# Deck_SchV1.net
KiCad netlist of a schematic drawn in Altium Designer
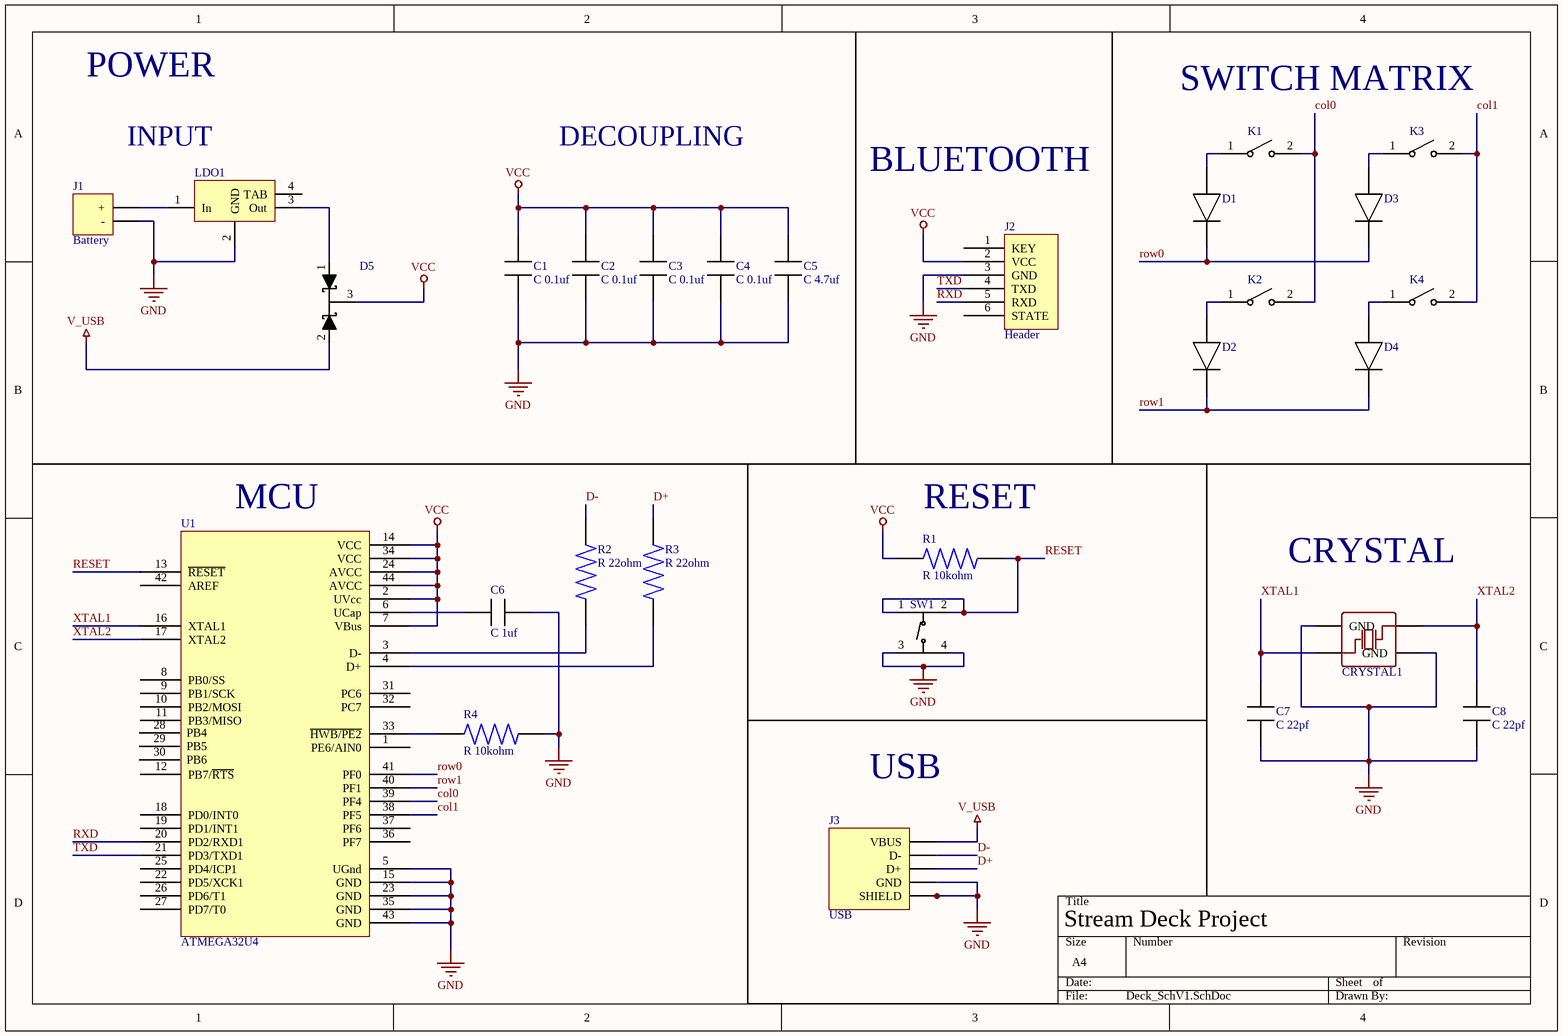
[diagram p0: Deck_SchV1.SchDoc]

(export (version "E")
  (design (tool "Eeschema 10.0.6"))
  (components
    (comp (ref "C1")
      (value "C 0.1uf")
      (footprint "C0805")
      (fields
        (field (name "MANUFACTURER") "Yageo")
        (field (name "MANUFACTURER PART NUMBER") "CC0805ZRY5V9BB104")
        (field (name "TOLERANCE") "80%")
      )
      (libsource (lib "Deck_SchlibV2") (part "CC0805ZRY5V9BB104"))
    )
    (comp (ref "C2")
      (value "C 0.1uf")
      (footprint "C0805")
      (fields
        (field (name "MANUFACTURER") "Yageo")
        (field (name "MANUFACTURER PART NUMBER") "CC0805ZRY5V9BB104")
        (field (name "TOLERANCE") "80%")
      )
      (libsource (lib "Deck_SchlibV2") (part "CC0805ZRY5V9BB104"))
    )
    (comp (ref "C3")
      (value "C 0.1uf")
      (footprint "C0805")
      (fields
        (field (name "MANUFACTURER") "Yageo")
        (field (name "MANUFACTURER PART NUMBER") "CC0805ZRY5V9BB104")
        (field (name "TOLERANCE") "80%")
      )
      (libsource (lib "Deck_SchlibV2") (part "CC0805ZRY5V9BB104"))
    )
    (comp (ref "C4")
      (value "C 0.1uf")
      (footprint "C0805")
      (fields
        (field (name "MANUFACTURER") "Yageo")
        (field (name "MANUFACTURER PART NUMBER") "CC0805ZRY5V9BB104")
        (field (name "TOLERANCE") "80%")
      )
      (libsource (lib "Deck_SchlibV2") (part "CC0805ZRY5V9BB104"))
    )
    (comp (ref "C5")
      (value "C 4.7uf")
      (footprint "C0805")
      (fields
        (field (name "MANUFACTURER") "Samsung")
        (field (name "MANUFACTURER PART NUMBER") "CL21A475KAQNNNE")
        (field (name "TOLERANCE") "10%")
      )
      (libsource (lib "Deck_SchlibV2") (part "CL21A475KAQNNNE"))
    )
    (comp (ref "C6")
      (value "C 1uf")
      (footprint "C0805")
      (fields
        (field (name "MANUFACTURER") "Samsung")
        (field (name "MANUFACTURER PART NUMBER") "CL21B105KBFNNNE")
        (field (name "TOLERANCE") "10%")
      )
      (libsource (lib "Deck_SchlibV2") (part "CL21B105KBFNNNE"))
    )
    (comp (ref "C7")
      (value "C 22pf")
      (footprint "C0805")
      (description "Cap Ceramic 22pF 50V C0G 5% SMD 0805 125C T/R")
      (fields
        (field (name "MANUFACTURER") "Samsung")
        (field (name "MANUFACTURER PART NUMBER") "CL21C220JBANNNC")
      )
      (libsource (lib "Deck_SchlibV2") (part "CL21C220JBANNNC"))
    )
    (comp (ref "C8")
      (value "C 22pf")
      (footprint "C0805")
      (description "Cap Ceramic 22pF 50V C0G 5% SMD 0805 125C T/R")
      (fields
        (field (name "MANUFACTURER") "Samsung")
        (field (name "MANUFACTURER PART NUMBER") "CL21C220JBANNNC")
      )
      (libsource (lib "Deck_SchlibV2") (part "CL21C220JBANNNC"))
    )
    (comp (ref "CRYSTAL1")
      (value "Crystal")
      (footprint "CRYSTAL-SMD_4P-L3.2-W2.5-BL")
      (fields (field (name "MANUFACTURER") "Seiko") (field (name "MANUFACTURER PART NUMBER") "X1E0000210264"))
      (libsource (lib "Deck_SchlibV2") (part "X1E0000210264"))
    )
    (comp (ref "D1")
      (value "Diode")
      (footprint "Diode")
      (description "MICRO COMMERCIAL COMPONENTS - 1N4148W-TP - SWITCHING DIODE, 150mA, 100V, SOD123, FU")
      (fields (field (name "MANUFACTURER") "MCC") (field (name "MANUFACTURER PART NUMBER") "1N4148W-TP"))
      (libsource (lib "Deck_SchlibV2") (part "1N4148W-TP"))
    )
    (comp (ref "D2")
      (value "Diode")
      (footprint "Diode")
      (description "MICRO COMMERCIAL COMPONENTS - 1N4148W-TP - SWITCHING DIODE, 150mA, 100V, SOD123, FU")
      (fields (field (name "MANUFACTURER") "MCC") (field (name "MANUFACTURER PART NUMBER") "1N4148W-TP"))
      (libsource (lib "Deck_SchlibV2") (part "1N4148W-TP"))
    )
    (comp (ref "D3")
      (value "Diode")
      (footprint "Diode")
      (description "MICRO COMMERCIAL COMPONENTS - 1N4148W-TP - SWITCHING DIODE, 150mA, 100V, SOD123, FU")
      (fields (field (name "MANUFACTURER") "MCC") (field (name "MANUFACTURER PART NUMBER") "1N4148W-TP"))
      (libsource (lib "Deck_SchlibV2") (part "1N4148W-TP"))
    )
    (comp (ref "D4")
      (value "Diode")
      (footprint "Diode")
      (description "MICRO COMMERCIAL COMPONENTS - 1N4148W-TP - SWITCHING DIODE, 150mA, 100V, SOD123, FU")
      (fields (field (name "MANUFACTURER") "MCC") (field (name "MANUFACTURER PART NUMBER") "1N4148W-TP"))
      (libsource (lib "Deck_SchlibV2") (part "1N4148W-TP"))
    )
    (comp (ref "D5")
      (value "Schottky diode")
      (footprint "SOT95P237X111-3N")
      (description "Diode Schottky 30V 0.2A 3-Pin SOT-23 T/R")
      (fields
        (field (name "MANUFACTURER") "ON Semiconductor")
        (field (name "MANUFACTURER PART NUMBER") "BAT54CLT1G")
      )
      (libsource (lib "Deck_SchlibV2") (part "BAT54CLT1G"))
    )
    (comp (ref "J1")
      (value "Battery")
      (footprint "HDR-TH_2P-P2.54-V-M-1")
      (description "CONN HEADER VERT 2POS 2.54MM")
      (fields (field (name "MANUFACTURER") "Molex") (field (name "MANUFACTURER PART NUMBER") "22-28-4020"))
      (libsource (lib "Deck_SchlibV2") (part "22-28-4020"))
    )
    (comp (ref "J2")
      (value "Header")
      (footprint "HDR-TH_6P-P2.54-H-W8.6_A2541HWR-6P")
      (fields
        (field (name "MANUFACTURER") "CJT Connectors")
        (field (name "MANUFACTURER PART NUMBER") "A2541HWR-6P")
      )
      (libsource (lib "Deck_SchlibV2") (part "A2541HWR-6P"))
    )
    (comp (ref "J3")
      (value "USB")
      (footprint "USB")
      (description "Conn Mini USB 2.0 Type B RCP 5 POS 0.8mm Solder RA SMD 5 Terminal 1 Port Embossed T/R")
      (fields
        (field (name "MANUFACTURER") "Hirose")
        (field (name "MANUFACTURER PART NUMBER") "UX60SC-MB-5S8")
      )
      (libsource (lib "Deck_SchlibV2") (part "UX60SC-MB-5S8"))
    )
    (comp (ref "K1")
      (value "Switch")
      (footprint "Mx_Alps_100")
      (libsource (lib "Deck_SchlibV2") (part "Keyboard Switch"))
    )
    (comp (ref "K2")
      (value "Switch")
      (footprint "Mx_Alps_100")
      (libsource (lib "Deck_SchlibV2") (part "Keyboard Switch"))
    )
    (comp (ref "K3")
      (value "Switch")
      (footprint "Mx_Alps_100")
      (libsource (lib "Deck_SchlibV2") (part "Keyboard Switch"))
    )
    (comp (ref "K4")
      (value "Switch")
      (footprint "Mx_Alps_100")
      (libsource (lib "Deck_SchlibV2") (part "Keyboard Switch"))
    )
    (comp (ref "LDO1")
      (value "5V regulator")
      (footprint "SOT-223_L6.5-W3.5-P2.30-LS7.0-BR")
      (fields
        (field (name "MANUFACTURER") "Advanced Monolithic Systems")
        (field (name "MANUFACTURER PART NUMBER") "AMS1117-5.0")
      )
      (libsource (lib "Deck_SchlibV2") (part "AMS1117-5.0"))
    )
    (comp (ref "R1")
      (value "R 10kohm")
      (footprint "R0805")
      (fields
        (field (name "MANUFACTURER") "Uniroyal")
        (field (name "MANUFACTURER PART NUMBER") "0805W8F1002T5E")
      )
      (libsource (lib "Deck_SchlibV2") (part "0805W8F1002T5E"))
    )
    (comp (ref "R2")
      (value "R 22ohm")
      (footprint "R0805")
      (fields
        (field (name "MANUFACTURER") "Uniroyal")
        (field (name "MANUFACTURER PART NUMBER") "0805W8F220JT5E")
      )
      (libsource (lib "Deck_SchlibV2") (part "0805W8F220JT5E"))
    )
    (comp (ref "R3")
      (value "R 22ohm")
      (footprint "R0805")
      (fields
        (field (name "MANUFACTURER") "Uniroyal")
        (field (name "MANUFACTURER PART NUMBER") "0805W8F220JT5E")
      )
      (libsource (lib "Deck_SchlibV2") (part "0805W8F220JT5E"))
    )
    (comp (ref "R4")
      (value "R 10kohm")
      (footprint "R0805")
      (fields
        (field (name "MANUFACTURER") "Uniroyal")
        (field (name "MANUFACTURER PART NUMBER") "0805W8F1002T5E")
      )
      (libsource (lib "Deck_SchlibV2") (part "0805W8F1002T5E"))
    )
    (comp (ref "SW1")
      (value "Button")
      (footprint "SW-SMD_4P-L5.1-W5.1-P3.70-LS6.5-TL-2")
      (fields
        (field (name "MANUFACTURER") "XKB Connectivity")
        (field (name "MANUFACTURER PART NUMBER") "TS-1187A-B-A-B")
      )
      (libsource (lib "Deck_SchlibV2") (part "TS-1187A-B-A-B"))
    )
    (comp (ref "U1")
      (value "ATMEGA32U4")
      (footprint "ATMEGA32U2-AUR")
      (description "IC MCU 8BIT 32KB FLASH 32TQFP")
      (fields
        (field (name "MANUFACTURER") "Microchip / Atmel")
        (field (name "MANUFACTURER PART NUMBER") "ATMEGA32U2-AUR")
      )
      (libsource (lib "Deck_SchlibV2") (part "ATMEGA32U2-AUR"))
    )
  )
  (nets
    (net (code "1") (name "/D+") (class "Default")
      (node (ref "J3") (pin "3") (pinfunction "D+_3") (pintype "passive"))
      (node (ref "R3") (pin "2") (pinfunction "57_2") (pintype "passive"))
    )
    (net (code "2") (name "/D-") (class "Default")
      (node (ref "J3") (pin "2") (pinfunction "D-_2") (pintype "passive"))
      (node (ref "R2") (pin "2") (pinfunction "57_2") (pintype "passive"))
    )
    (net (code "3") (name "/RESET") (class "Default")
      (node (ref "R1") (pin "2") (pinfunction "57_2") (pintype "passive"))
      (node (ref "SW1") (pin "1") (pinfunction "A_1") (pintype "passive"))
      (node (ref "SW1") (pin "2") (pinfunction "B_2") (pintype "passive"))
      (node (ref "U1") (pin "13") (pinfunction "~{RESET}_13") (pintype "passive"))
    )
    (net (code "4") (name "/RXD") (class "Default")
      (node (ref "J2") (pin "5") (pinfunction "RXD_5") (pintype "passive"))
      (node (ref "U1") (pin "20") (pinfunction "PD2/RXD1_20") (pintype "passive"))
    )
    (net (code "5") (name "/TXD") (class "Default")
      (node (ref "J2") (pin "4") (pinfunction "TXD_4") (pintype "passive"))
      (node (ref "U1") (pin "21") (pinfunction "PD3/TXD1_21") (pintype "passive"))
    )
    (net (code "6") (name "/XTAL1") (class "Default")
      (node (ref "C7") (pin "2") (pinfunction "54_2") (pintype "passive"))
      (node (ref "CRYSTAL1") (pin "1") (pinfunction "OSC1_1") (pintype "passive"))
      (node (ref "U1") (pin "16") (pinfunction "XTAL1_16") (pintype "passive"))
    )
    (net (code "7") (name "/XTAL2") (class "Default")
      (node (ref "C8") (pin "2") (pinfunction "54_2") (pintype "passive"))
      (node (ref "CRYSTAL1") (pin "3") (pinfunction "OSC2_3") (pintype "passive"))
      (node (ref "U1") (pin "17") (pinfunction "XTAL2_17") (pintype "passive"))
    )
    (net (code "8") (name "/col0") (class "Default")
      (node (ref "K1") (pin "2") (pinfunction "2_2") (pintype "passive"))
      (node (ref "K2") (pin "2") (pinfunction "2_2") (pintype "passive"))
      (node (ref "U1") (pin "39") (pinfunction "PF4_39") (pintype "passive"))
    )
    (net (code "9") (name "/col1") (class "Default")
      (node (ref "K3") (pin "2") (pinfunction "2_2") (pintype "passive"))
      (node (ref "K4") (pin "2") (pinfunction "2_2") (pintype "passive"))
      (node (ref "U1") (pin "38") (pinfunction "PF5_38") (pintype "passive"))
    )
    (net (code "10") (name "/row0") (class "Default")
      (node (ref "D1") (pin "2") (pinfunction "-_2") (pintype "passive"))
      (node (ref "D3") (pin "2") (pinfunction "-_2") (pintype "passive"))
      (node (ref "U1") (pin "41") (pinfunction "PF0_41") (pintype "passive"))
    )
    (net (code "11") (name "/row1") (class "Default")
      (node (ref "D2") (pin "2") (pinfunction "-_2") (pintype "passive"))
      (node (ref "D4") (pin "2") (pinfunction "-_2") (pintype "passive"))
      (node (ref "U1") (pin "40") (pinfunction "PF1_40") (pintype "passive"))
    )
    (net (code "12") (name "GND") (class "Default")
      (node (ref "C1") (pin "1") (pinfunction "55_1") (pintype "passive"))
      (node (ref "C2") (pin "1") (pinfunction "55_1") (pintype "passive"))
      (node (ref "C3") (pin "1") (pinfunction "55_1") (pintype "passive"))
      (node (ref "C4") (pin "1") (pinfunction "55_1") (pintype "passive"))
      (node (ref "C5") (pin "1") (pinfunction "55_1") (pintype "passive"))
      (node (ref "C6") (pin "1") (pinfunction "55_1") (pintype "passive"))
      (node (ref "C7") (pin "1") (pinfunction "55_1") (pintype "passive"))
      (node (ref "C8") (pin "1") (pinfunction "55_1") (pintype "passive"))
      (node (ref "CRYSTAL1") (pin "2") (pinfunction "GND_2") (pintype "passive"))
      (node (ref "CRYSTAL1") (pin "4") (pinfunction "GND_4") (pintype "passive"))
      (node (ref "J1") (pin "2") (pinfunction "-_2") (pintype "passive"))
      (node (ref "J2") (pin "3") (pinfunction "GND_3") (pintype "passive"))
      (node (ref "J3") (pin "4") (pinfunction "GND_4") (pintype "passive"))
      (node (ref "J3") (pin "5") (pinfunction "SHIELD_5") (pintype "passive"))
      (node (ref "J3") (pin "S1") (pinfunction "6_S1") (pintype "passive"))
      (node (ref "J3") (pin "S2") (pinfunction "6_S2") (pintype "passive"))
      (node (ref "J3") (pin "S3") (pinfunction "6_S3") (pintype "passive"))
      (node (ref "J3") (pin "S4") (pinfunction "6_S4") (pintype "passive"))
      (node (ref "LDO1") (pin "2") (pinfunction "GND_2") (pintype "passive"))
      (node (ref "R4") (pin "2") (pinfunction "57_2") (pintype "passive"))
      (node (ref "SW1") (pin "3") (pinfunction "C_3") (pintype "passive"))
      (node (ref "SW1") (pin "4") (pinfunction "D_4") (pintype "passive"))
      (node (ref "U1") (pin "15") (pinfunction "GND_15") (pintype "passive"))
      (node (ref "U1") (pin "23") (pinfunction "GND_23") (pintype "passive"))
      (node (ref "U1") (pin "35") (pinfunction "GND_35") (pintype "passive"))
      (node (ref "U1") (pin "43") (pinfunction "GND_43") (pintype "passive"))
      (node (ref "U1") (pin "5") (pinfunction "UGnd_5") (pintype "passive"))
    )
    (net (code "13") (name "Net-(C6-54)") (class "Default")
      (node (ref "C6") (pin "2") (pinfunction "54_2") (pintype "passive"))
      (node (ref "U1") (pin "6") (pinfunction "UCap_6") (pintype "passive"))
    )
    (net (code "14") (name "Net-(D1-+)") (class "Default")
      (node (ref "D1") (pin "1") (pinfunction "+_1") (pintype "passive"))
      (node (ref "K1") (pin "1") (pinfunction "1_1") (pintype "passive"))
    )
    (net (code "15") (name "Net-(D2-+)") (class "Default")
      (node (ref "D2") (pin "1") (pinfunction "+_1") (pintype "passive"))
      (node (ref "K2") (pin "1") (pinfunction "1_1") (pintype "passive"))
    )
    (net (code "16") (name "Net-(D3-+)") (class "Default")
      (node (ref "D3") (pin "1") (pinfunction "+_1") (pintype "passive"))
      (node (ref "K3") (pin "1") (pinfunction "1_1") (pintype "passive"))
    )
    (net (code "17") (name "Net-(D4-+)") (class "Default")
      (node (ref "D4") (pin "1") (pinfunction "+_1") (pintype "passive"))
      (node (ref "K4") (pin "1") (pinfunction "1_1") (pintype "passive"))
    )
    (net (code "18") (name "Net-(D5-64)") (class "Default")
      (node (ref "D5") (pin "1") (pinfunction "64_1") (pintype "passive"))
      (node (ref "LDO1") (pin "3") (pinfunction "Out_3") (pintype "passive"))
    )
    (net (code "19") (name "Net-(J1-+)") (class "Default")
      (node (ref "J1") (pin "1") (pinfunction "+_1") (pintype "passive"))
      (node (ref "LDO1") (pin "1") (pinfunction "In_1") (pintype "passive"))
    )
    (net (code "20") (name "Net-(R2-56)") (class "Default")
      (node (ref "R2") (pin "1") (pinfunction "56_1") (pintype "passive"))
      (node (ref "U1") (pin "3") (pinfunction "D-_3") (pintype "passive"))
    )
    (net (code "21") (name "Net-(R3-56)") (class "Default")
      (node (ref "R3") (pin "1") (pinfunction "56_1") (pintype "passive"))
      (node (ref "U1") (pin "4") (pinfunction "D+_4") (pintype "passive"))
    )
    (net (code "22") (name "Net-(R4-56)") (class "Default")
      (node (ref "R4") (pin "1") (pinfunction "56_1") (pintype "passive"))
      (node (ref "U1") (pin "33") (pinfunction "~{HWB/PE2}_33") (pintype "passive"))
    )
    (net (code "23") (name "VCC") (class "Default")
      (node (ref "C1") (pin "2") (pinfunction "54_2") (pintype "passive"))
      (node (ref "C2") (pin "2") (pinfunction "54_2") (pintype "passive"))
      (node (ref "C3") (pin "2") (pinfunction "54_2") (pintype "passive"))
      (node (ref "C4") (pin "2") (pinfunction "54_2") (pintype "passive"))
      (node (ref "C5") (pin "2") (pinfunction "54_2") (pintype "passive"))
      (node (ref "D5") (pin "3") (pinfunction "66_3") (pintype "passive"))
      (node (ref "J2") (pin "2") (pinfunction "VCC_2") (pintype "passive"))
      (node (ref "R1") (pin "1") (pinfunction "56_1") (pintype "passive"))
      (node (ref "U1") (pin "14") (pinfunction "VCC_14") (pintype "passive"))
      (node (ref "U1") (pin "2") (pinfunction "UVcc_2") (pintype "passive"))
      (node (ref "U1") (pin "24") (pinfunction "AVCC_24") (pintype "passive"))
      (node (ref "U1") (pin "34") (pinfunction "VCC_34") (pintype "passive"))
      (node (ref "U1") (pin "44") (pinfunction "AVCC_44") (pintype "passive"))
      (node (ref "U1") (pin "7") (pinfunction "VBus_7") (pintype "passive"))
    )
    (net (code "24") (name "V_USB") (class "Default")
      (node (ref "D5") (pin "2") (pinfunction "65_2") (pintype "passive"))
      (node (ref "J3") (pin "1") (pinfunction "VBUS_1") (pintype "passive"))
    )
    (net (code "25") (name "unconnected-(J2-KEY-Pad1)") (class "Default")
      (node (ref "J2") (pin "1") (pinfunction "KEY_1") (pintype "passive"))
    )
    (net (code "26") (name "unconnected-(J2-STATE-Pad6)") (class "Default")
      (node (ref "J2") (pin "6") (pinfunction "STATE_6") (pintype "passive"))
    )
    (net (code "27") (name "unconnected-(LDO1-TAB-Pad4)") (class "Default")
      (node (ref "LDO1") (pin "4") (pinfunction "TAB_4") (pintype "passive"))
    )
    (net (code "28") (name "unconnected-(U1-AREF-Pad42)") (class "Default")
      (node (ref "U1") (pin "42") (pinfunction "AREF_42") (pintype "passive"))
    )
    (net (code "29") (name "unconnected-(U1-PB0{slash}SS-Pad8)") (class "Default")
      (node (ref "U1") (pin "8") (pinfunction "PB0/SS_8") (pintype "passive"))
    )
    (net (code "30") (name "unconnected-(U1-PB1{slash}SCK-Pad9)") (class "Default")
      (node (ref "U1") (pin "9") (pinfunction "PB1/SCK_9") (pintype "passive"))
    )
    (net (code "31") (name "unconnected-(U1-PB2{slash}MOSI-Pad10)") (class "Default")
      (node (ref "U1") (pin "10") (pinfunction "PB2/MOSI_10") (pintype "passive"))
    )
    (net (code "32") (name "unconnected-(U1-PB3{slash}MISO-Pad11)") (class "Default")
      (node (ref "U1") (pin "11") (pinfunction "PB3/MISO_11") (pintype "passive"))
    )
    (net (code "33") (name "unconnected-(U1-PB4-Pad28)") (class "Default")
      (node (ref "U1") (pin "28") (pinfunction "PB4_28") (pintype "passive"))
    )
    (net (code "34") (name "unconnected-(U1-PB5-Pad29)") (class "Default")
      (node (ref "U1") (pin "29") (pinfunction "PB5_29") (pintype "passive"))
    )
    (net (code "35") (name "unconnected-(U1-PB6-Pad30)") (class "Default")
      (node (ref "U1") (pin "30") (pinfunction "PB6_30") (pintype "passive"))
    )
    (net (code "36") (name "unconnected-(U1-PB7{slash}~{RTS}-Pad12)") (class "Default")
      (node (ref "U1") (pin "12") (pinfunction "PB7/~{RTS}_12") (pintype "passive"))
    )
    (net (code "37") (name "unconnected-(U1-PC6-Pad31)") (class "Default")
      (node (ref "U1") (pin "31") (pinfunction "PC6_31") (pintype "passive"))
    )
    (net (code "38") (name "unconnected-(U1-PC7-Pad32)") (class "Default")
      (node (ref "U1") (pin "32") (pinfunction "PC7_32") (pintype "passive"))
    )
    (net (code "39") (name "unconnected-(U1-PD0{slash}INT0-Pad18)") (class "Default")
      (node (ref "U1") (pin "18") (pinfunction "PD0/INT0_18") (pintype "passive"))
    )
    (net (code "40") (name "unconnected-(U1-PD1{slash}INT1-Pad19)") (class "Default")
      (node (ref "U1") (pin "19") (pinfunction "PD1/INT1_19") (pintype "passive"))
    )
    (net (code "41") (name "unconnected-(U1-PD4{slash}ICP1-Pad25)") (class "Default")
      (node (ref "U1") (pin "25") (pinfunction "PD4/ICP1_25") (pintype "passive"))
    )
    (net (code "42") (name "unconnected-(U1-PD5{slash}XCK1-Pad22)") (class "Default")
      (node (ref "U1") (pin "22") (pinfunction "PD5/XCK1_22") (pintype "passive"))
    )
    (net (code "43") (name "unconnected-(U1-PD6{slash}T1-Pad26)") (class "Default")
      (node (ref "U1") (pin "26") (pinfunction "PD6/T1_26") (pintype "passive"))
    )
    (net (code "44") (name "unconnected-(U1-PD7{slash}T0-Pad27)") (class "Default")
      (node (ref "U1") (pin "27") (pinfunction "PD7/T0_27") (pintype "passive"))
    )
    (net (code "45") (name "unconnected-(U1-PE6{slash}AIN0-Pad1)") (class "Default")
      (node (ref "U1") (pin "1") (pinfunction "PE6/AIN0_1") (pintype "passive"))
    )
    (net (code "46") (name "unconnected-(U1-PF6-Pad37)") (class "Default")
      (node (ref "U1") (pin "37") (pinfunction "PF6_37") (pintype "passive"))
    )
    (net (code "47") (name "unconnected-(U1-PF7-Pad36)") (class "Default")
      (node (ref "U1") (pin "36") (pinfunction "PF7_36") (pintype "passive"))
    )
  )
)
